# XCOMBO.net
KiCad netlist of a schematic drawn in EAGLE
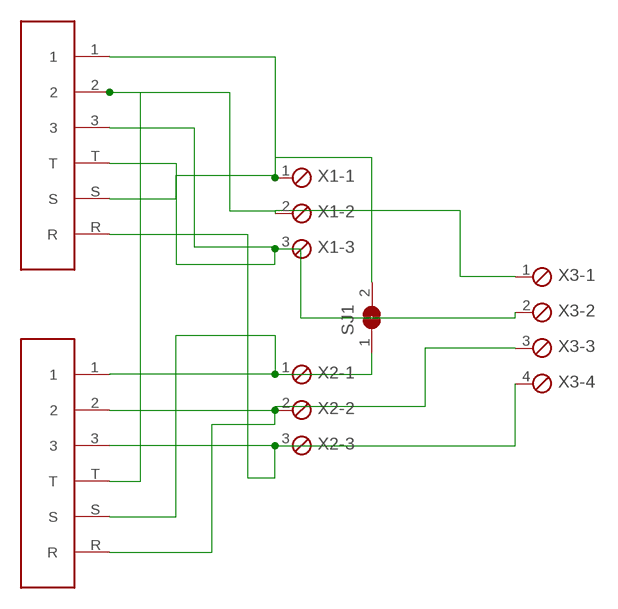
[diagram p0: schematic, sheet 1]

(export (version "E")
  (design (tool "Eeschema 10.0.6"))
  (components
    (comp (ref "SJ1") (value "SJ") (footprint "eagle-import:SJ") (libsource (lib "eagle-import") (part "SJ")))
    (comp (ref "U$1")
      (value "XLRCOMBO")
      (footprint "eagle-import:NCJ6FI-S-0")
      (libsource (lib "eagle-import") (part "XLRCOMBO"))
    )
    (comp (ref "U$2")
      (value "XLRCOMBO")
      (footprint "eagle-import:NCJ6FI-S-0")
      (libsource (lib "eagle-import") (part "XLRCOMBO"))
    )
    (comp (ref "X1")
      (value "MPT3")
      (footprint "eagle-import:3POL254")
      (libsource (lib "eagle-import") (part "MPT3"))
    )
    (comp (ref "X2")
      (value "MPT3")
      (footprint "eagle-import:3POL254")
      (libsource (lib "eagle-import") (part "MPT3"))
    )
    (comp (ref "X3")
      (value "MPT4")
      (footprint "eagle-import:4POL254")
      (libsource (lib "eagle-import") (part "MPT4"))
    )
  )
  (nets
    (net (code "1") (name "Net-(SJ1-Pad1)") (class "Default")
      (node (ref "SJ1") (pin "1") (pinfunction "1_1") (pintype "passive"))
      (node (ref "U$1") (pin "1") (pinfunction "1_1") (pintype "bidirectional"))
      (node (ref "U$1") (pin "S") (pinfunction "S_S") (pintype "bidirectional"))
      (node (ref "X2") (pin "1") (pinfunction "1_1") (pintype "passive"))
    )
    (net (code "2") (name "Net-(SJ1-Pad2)") (class "Default")
      (node (ref "SJ1") (pin "2") (pinfunction "2_2") (pintype "passive"))
      (node (ref "U$2") (pin "1") (pinfunction "1_1") (pintype "bidirectional"))
      (node (ref "U$2") (pin "S") (pinfunction "S_S") (pintype "bidirectional"))
      (node (ref "X1") (pin "1") (pinfunction "1_1") (pintype "passive"))
    )
    (net (code "3") (name "Net-(X1B-1)") (class "Default")
      (node (ref "U$1") (pin "T") (pinfunction "T_T") (pintype "bidirectional"))
      (node (ref "U$2") (pin "2") (pinfunction "2_2") (pintype "bidirectional"))
      (node (ref "X1") (pin "2") (pinfunction "1_2") (pintype "passive"))
      (node (ref "X3") (pin "1") (pinfunction "1_1") (pintype "passive"))
    )
    (net (code "4") (name "Net-(X1C-1)") (class "Default")
      (node (ref "U$2") (pin "3") (pinfunction "3_3") (pintype "bidirectional"))
      (node (ref "U$2") (pin "T") (pinfunction "T_T") (pintype "bidirectional"))
      (node (ref "X1") (pin "3") (pinfunction "1_3") (pintype "passive"))
      (node (ref "X3") (pin "2") (pinfunction "1_2") (pintype "passive"))
    )
    (net (code "5") (name "Net-(X2B-1)") (class "Default")
      (node (ref "U$1") (pin "2") (pinfunction "2_2") (pintype "bidirectional"))
      (node (ref "U$1") (pin "R") (pinfunction "R_R") (pintype "bidirectional"))
      (node (ref "X2") (pin "2") (pinfunction "1_2") (pintype "passive"))
      (node (ref "X3") (pin "3") (pinfunction "1_3") (pintype "passive"))
    )
    (net (code "6") (name "Net-(X2C-1)") (class "Default")
      (node (ref "U$1") (pin "3") (pinfunction "3_3") (pintype "bidirectional"))
      (node (ref "U$2") (pin "R") (pinfunction "R_R") (pintype "bidirectional"))
      (node (ref "X2") (pin "3") (pinfunction "1_3") (pintype "passive"))
      (node (ref "X3") (pin "4") (pinfunction "1_4") (pintype "passive"))
    )
  )
)
